# pca10056_sheet3_pin_map.net
KiCad netlist of a schematic drawn in Altium Designer
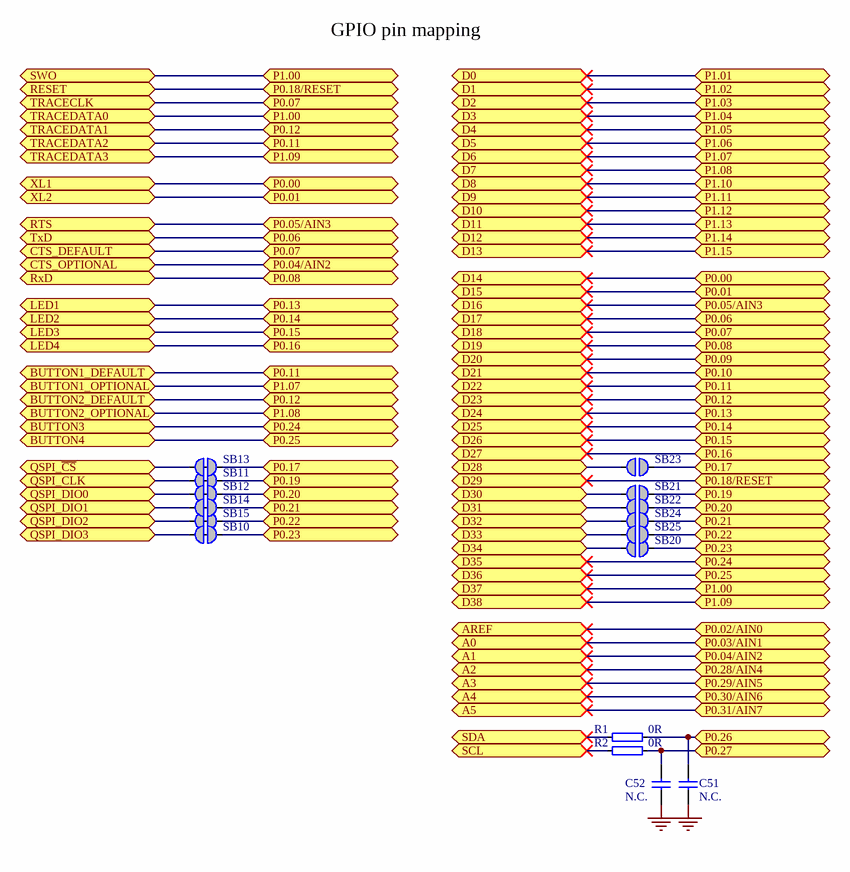
[diagram p0: pca10056_sheet3_pin_map.SchDoc]

(export (version "E")
  (design (tool "Eeschema 10.0.6"))
  (components
    (comp (ref "C51")
      (value "N.C.")
      (footprint "CAPC1005X04L")
      (description "Not mounted")
      (fields (field (name "PART NUMBER") "C0402-N.C.") (field (name "PUBLISHER") "Nordic Semiconductor"))
      (libsource (lib "Nordic Passive DB") (part "CAP"))
    )
    (comp (ref "C52")
      (value "N.C.")
      (footprint "CAPC1005X04L")
      (description "Not mounted")
      (fields (field (name "PART NUMBER") "C0402-N.C.") (field (name "PUBLISHER") "Nordic Semiconductor"))
      (libsource (lib "Nordic Passive DB") (part "CAP"))
    )
    (comp (ref "R1")
      (value "0R")
      (footprint "RESC1005X04L")
      (description "Resistor, ±5%, 0.063W")
      (fields (field (name "PART NUMBER") "R0402-0R") (field (name "PUBLISHER") "Nordic Semiconductor"))
      (libsource (lib "Nordic Passive DB") (part "RES_1"))
    )
    (comp (ref "R2")
      (value "0R")
      (footprint "RESC1005X04L")
      (description "Resistor, ±5%, 0.063W")
      (fields (field (name "PART NUMBER") "R0402-0R") (field (name "PUBLISHER") "Nordic Semiconductor"))
      (libsource (lib "Nordic Passive DB") (part "RES_1"))
    )
    (comp (ref "SB10")
      (value "Solderbridge")
      (footprint "Solderbridge_Shorted")
      (description "Shorted Solderbridge")
      (fields
        (field (name "PART NUMBER") "Solderbridge Shorted")
        (field (name "PUBLISHER") "Nordic Semiconductor")
      )
      (libsource (lib "Nordic Passive DB") (part "SOLDERBRIDGE_SHORTED"))
    )
    (comp (ref "SB11")
      (value "Solderbridge")
      (footprint "Solderbridge_Shorted")
      (description "Shorted Solderbridge")
      (fields
        (field (name "PART NUMBER") "Solderbridge Shorted")
        (field (name "PUBLISHER") "Nordic Semiconductor")
      )
      (libsource (lib "Nordic Passive DB") (part "SOLDERBRIDGE_SHORTED"))
    )
    (comp (ref "SB12")
      (value "Solderbridge")
      (footprint "Solderbridge_Shorted")
      (description "Shorted Solderbridge")
      (fields
        (field (name "PART NUMBER") "Solderbridge Shorted")
        (field (name "PUBLISHER") "Nordic Semiconductor")
      )
      (libsource (lib "Nordic Passive DB") (part "SOLDERBRIDGE_SHORTED"))
    )
    (comp (ref "SB13")
      (value "Solderbridge")
      (footprint "Solderbridge_Shorted")
      (description "Shorted Solderbridge")
      (fields
        (field (name "PART NUMBER") "Solderbridge Shorted")
        (field (name "PUBLISHER") "Nordic Semiconductor")
      )
      (libsource (lib "Nordic Passive DB") (part "SOLDERBRIDGE_SHORTED"))
    )
    (comp (ref "SB14")
      (value "Solderbridge")
      (footprint "Solderbridge_Shorted")
      (description "Shorted Solderbridge")
      (fields
        (field (name "PART NUMBER") "Solderbridge Shorted")
        (field (name "PUBLISHER") "Nordic Semiconductor")
      )
      (libsource (lib "Nordic Passive DB") (part "SOLDERBRIDGE_SHORTED"))
    )
    (comp (ref "SB15")
      (value "Solderbridge")
      (footprint "Solderbridge_Shorted")
      (description "Shorted Solderbridge")
      (fields
        (field (name "PART NUMBER") "Solderbridge Shorted")
        (field (name "PUBLISHER") "Nordic Semiconductor")
      )
      (libsource (lib "Nordic Passive DB") (part "SOLDERBRIDGE_SHORTED"))
    )
    (comp (ref "SB20")
      (value "Solderbridge")
      (footprint "Solderbridge")
      (fields (field (name "PUBLISHER") "Nordic Semiconductor"))
      (libsource (lib "Nordic Passive DB") (part "SOLDERBRIDGE"))
    )
    (comp (ref "SB21")
      (value "Solderbridge")
      (footprint "Solderbridge")
      (fields (field (name "PUBLISHER") "Nordic Semiconductor"))
      (libsource (lib "Nordic Passive DB") (part "SOLDERBRIDGE"))
    )
    (comp (ref "SB22")
      (value "Solderbridge")
      (footprint "Solderbridge")
      (fields (field (name "PUBLISHER") "Nordic Semiconductor"))
      (libsource (lib "Nordic Passive DB") (part "SOLDERBRIDGE"))
    )
    (comp (ref "SB23")
      (value "Solderbridge")
      (footprint "Solderbridge")
      (fields (field (name "PUBLISHER") "Nordic Semiconductor"))
      (libsource (lib "Nordic Passive DB") (part "SOLDERBRIDGE"))
    )
    (comp (ref "SB24")
      (value "Solderbridge")
      (footprint "Solderbridge")
      (fields (field (name "PUBLISHER") "Nordic Semiconductor"))
      (libsource (lib "Nordic Passive DB") (part "SOLDERBRIDGE"))
    )
    (comp (ref "SB25")
      (value "Solderbridge")
      (footprint "Solderbridge")
      (fields (field (name "PUBLISHER") "Nordic Semiconductor"))
      (libsource (lib "Nordic Passive DB") (part "SOLDERBRIDGE"))
    )
  )
  (nets
    (net (code "38") (name "/D28") (class "Default")
      (node (ref "SB23") (pin "2") (pinfunction "1_2") (pintype "passive"))
    )
    (net (code "40") (name "/D30") (class "Default")
      (node (ref "SB21") (pin "2") (pinfunction "1_2") (pintype "passive"))
    )
    (net (code "41") (name "/D31") (class "Default")
      (node (ref "SB22") (pin "2") (pinfunction "1_2") (pintype "passive"))
    )
    (net (code "42") (name "/D32") (class "Default")
      (node (ref "SB24") (pin "2") (pinfunction "1_2") (pintype "passive"))
    )
    (net (code "43") (name "/D33") (class "Default")
      (node (ref "SB25") (pin "2") (pinfunction "1_2") (pintype "passive"))
    )
    (net (code "44") (name "/D34") (class "Default")
      (node (ref "SB20") (pin "2") (pinfunction "1_2") (pintype "passive"))
    )
    (net (code "47") (name "/P0.17") (class "Default")
      (node (ref "SB13") (pin "1") (pinfunction "0_1") (pintype "passive"))
      (node (ref "SB23") (pin "1") (pinfunction "0_1") (pintype "passive"))
    )
    (net (code "48") (name "/P0.19") (class "Default")
      (node (ref "SB11") (pin "1") (pinfunction "0_1") (pintype "passive"))
      (node (ref "SB21") (pin "1") (pinfunction "0_1") (pintype "passive"))
    )
    (net (code "49") (name "/P0.20") (class "Default")
      (node (ref "SB12") (pin "1") (pinfunction "0_1") (pintype "passive"))
      (node (ref "SB22") (pin "1") (pinfunction "0_1") (pintype "passive"))
    )
    (net (code "50") (name "/P0.21") (class "Default")
      (node (ref "SB14") (pin "1") (pinfunction "0_1") (pintype "passive"))
      (node (ref "SB24") (pin "1") (pinfunction "0_1") (pintype "passive"))
    )
    (net (code "51") (name "/P0.22") (class "Default")
      (node (ref "SB15") (pin "1") (pinfunction "0_1") (pintype "passive"))
      (node (ref "SB25") (pin "1") (pinfunction "0_1") (pintype "passive"))
    )
    (net (code "52") (name "/P0.23") (class "Default")
      (node (ref "SB10") (pin "1") (pinfunction "0_1") (pintype "passive"))
      (node (ref "SB20") (pin "1") (pinfunction "0_1") (pintype "passive"))
    )
    (net (code "53") (name "/P0.26") (class "Default")
      (node (ref "C51") (pin "2") (pinfunction "2_2") (pintype "passive"))
      (node (ref "R1") (pin "2") (pinfunction "2_2") (pintype "passive"))
    )
    (net (code "54") (name "/P0.27") (class "Default")
      (node (ref "C52") (pin "1") (pinfunction "1_1") (pintype "passive"))
      (node (ref "R2") (pin "2") (pinfunction "2_2") (pintype "passive"))
    )
    (net (code "55") (name "/QSPI_CLK") (class "Default")
      (node (ref "SB11") (pin "2") (pinfunction "1_2") (pintype "passive"))
    )
    (net (code "56") (name "/QSPI_DIO0") (class "Default")
      (node (ref "SB12") (pin "2") (pinfunction "1_2") (pintype "passive"))
    )
    (net (code "57") (name "/QSPI_DIO1") (class "Default")
      (node (ref "SB14") (pin "2") (pinfunction "1_2") (pintype "passive"))
    )
    (net (code "58") (name "/QSPI_DIO2") (class "Default")
      (node (ref "SB15") (pin "2") (pinfunction "1_2") (pintype "passive"))
    )
    (net (code "59") (name "/QSPI_DIO3") (class "Default")
      (node (ref "SB10") (pin "2") (pinfunction "1_2") (pintype "passive"))
    )
    (net (code "60") (name "/QSPI_~{CS}") (class "Default")
      (node (ref "SB13") (pin "2") (pinfunction "1_2") (pintype "passive"))
    )
    (net (code "61") (name "/SCL") (class "Default")
      (node (ref "R2") (pin "1") (pinfunction "1_1") (pintype "passive+no_connect"))
    )
    (net (code "62") (name "/SDA") (class "Default")
      (node (ref "R1") (pin "1") (pinfunction "1_1") (pintype "passive+no_connect"))
    )
    (net (code "63") (name "GND") (class "Default")
      (node (ref "C51") (pin "1") (pinfunction "1_1") (pintype "passive"))
      (node (ref "C52") (pin "2") (pinfunction "2_2") (pintype "passive"))
    )
  )
)
